# GATE_BOARD.net
KiCad netlist of a schematic drawn in Altium Designer
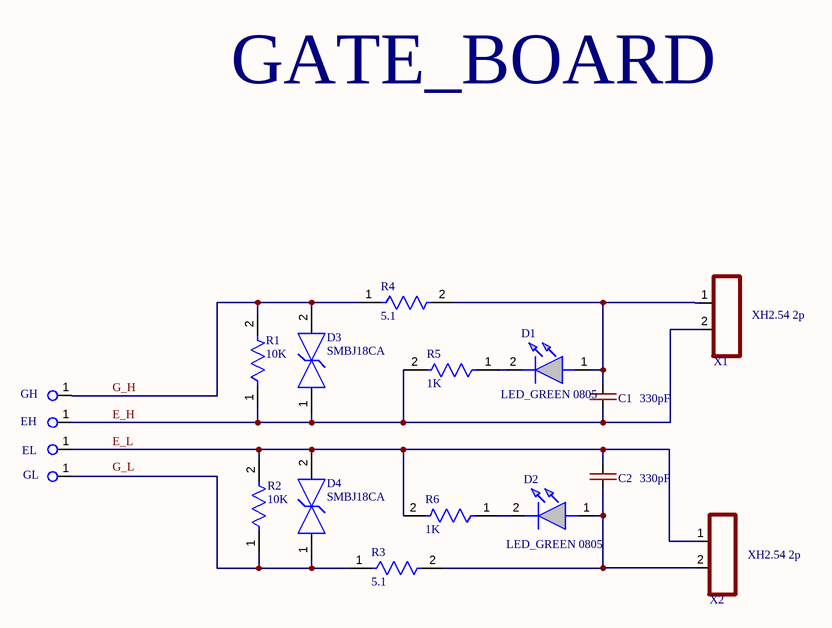
[diagram p0: GATE_BOARD.SchDoc]

(export (version "E")
  (design (tool "Eeschema 10.0.6"))
  (components
    (comp (ref "C1")
      (value "330pF")
      (footprint "CAP-0805")
      (libsource (lib "PASSIVE_COMPONENTS") (part "CAP-NON-POLAR"))
    )
    (comp (ref "C2")
      (value "330pF")
      (footprint "CAP-0805")
      (libsource (lib "PASSIVE_COMPONENTS") (part "CAP-NON-POLAR"))
    )
    (comp (ref "D1")
      (value "LED_GREEN 0805")
      (footprint "LED_GREEN")
      (fields
        (field (name "MANUFACTURER_PART_NUMBER") "151031YS06000")
        (field (name "MOUSER PART NUMBER") "710-151031YS06000")
      )
      (libsource (lib "Optic-LED") (part "LED"))
    )
    (comp (ref "D2")
      (value "LED_GREEN 0805")
      (footprint "LED_GREEN")
      (fields
        (field (name "MANUFACTURER_PART_NUMBER") "151031YS06000")
        (field (name "MOUSER PART NUMBER") "710-151031YS06000")
      )
      (libsource (lib "Optic-LED") (part "LED"))
    )
    (comp (ref "D3")
      (value "SMBJ18CA")
      (footprint "FP-SMBJ-MFG")
      (description "TVS DIODE 18V 29.2V DO214AA")
      (fields
        (field (name "MANUFACTURER") "Littelfuse Inc")
        (field (name "OCTOPART") "https://octopart.com/smbj18ca-littelfuse-350695")
      )
      (libsource (lib "Altium Content Vault") (part "876f4347bf90aa6f500f43e3cd03972"))
    )
    (comp (ref "D4")
      (value "SMBJ18CA")
      (footprint "FP-SMBJ-MFG")
      (description "TVS DIODE 18V 29.2V DO214AA")
      (fields
        (field (name "MANUFACTURER") "Littelfuse Inc")
        (field (name "OCTOPART") "https://octopart.com/smbj18ca-littelfuse-350695")
      )
      (libsource (lib "Altium Content Vault") (part "876f4347bf90aa6f500f43e3cd03972"))
    )
    (comp (ref "EH")
      (value "Test_Point_PCB")
      (footprint "Conn_Pad")
      (description "Test_Point")
      (libsource (lib "Connectors") (part "TP_PCB?"))
    )
    (comp (ref "EL")
      (value "Test_Point_PCB")
      (footprint "Conn_Pad")
      (description "Test_Point")
      (libsource (lib "Connectors") (part "TP_PCB?"))
    )
    (comp (ref "GL")
      (value "Test_Point_PCB")
      (footprint "Conn_Pad")
      (description "Test_Point")
      (libsource (lib "Connectors") (part "TP_PCB?"))
    )
    (comp (ref "R1")
      (value "10K")
      (footprint "RES-1206")
      (libsource (lib "PASSIVE_COMPONENTS") (part "RES-CONST"))
    )
    (comp (ref "R2")
      (value "10K")
      (footprint "RES-1206")
      (libsource (lib "PASSIVE_COMPONENTS") (part "RES-CONST"))
    )
    (comp (ref "R3")
      (value "5.1")
      (footprint "RES-2512")
      (libsource (lib "PASSIVE_COMPONENTS") (part "RES-CONST"))
    )
    (comp (ref "R4")
      (value "5.1")
      (footprint "RES-2512")
      (libsource (lib "PASSIVE_COMPONENTS") (part "RES-CONST"))
    )
    (comp (ref "R5")
      (value "1K")
      (footprint "RES-0805")
      (libsource (lib "PASSIVE_COMPONENTS") (part "RES-CONST"))
    )
    (comp (ref "R6")
      (value "1K")
      (footprint "RES-0805")
      (libsource (lib "PASSIVE_COMPONENTS") (part "RES-CONST"))
    )
    (comp (ref "TP4")
      (value "GH")
      (footprint "Conn_Pad")
      (description "Test_Point")
      (libsource (lib "Connectors") (part "TP_PCB?"))
    )
    (comp (ref "X1")
      (value "XH2.54 2p")
      (footprint "CONN-PLS-2-2.54mm")
      (libsource (lib "XH 2PIN") (part "CONN-2-PIN"))
    )
    (comp (ref "X2")
      (value "XH2.54 2p")
      (footprint "CONN-PLS-2-2.54mm")
      (libsource (lib "XH 2PIN") (part "CONN-2-PIN"))
    )
  )
  (nets
    (net (code "1") (name "/E_H") (class "Default")
      (node (ref "C1") (pin "1") (pinfunction "1_1") (pintype "passive"))
      (node (ref "D3") (pin "1") (pinfunction "1_1") (pintype "passive"))
      (node (ref "EH") (pin "1") (pinfunction "G9_1") (pintype "passive"))
      (node (ref "R1") (pin "1") (pinfunction "1_1") (pintype "passive"))
      (node (ref "R5") (pin "2") (pinfunction "2_2") (pintype "passive"))
      (node (ref "X1") (pin "2") (pinfunction "2_2") (pintype "passive"))
    )
    (net (code "2") (name "/E_L") (class "Default")
      (node (ref "C2") (pin "2") (pinfunction "2_2") (pintype "passive"))
      (node (ref "D4") (pin "2") (pinfunction "2_2") (pintype "passive"))
      (node (ref "EL") (pin "1") (pinfunction "G9_1") (pintype "passive"))
      (node (ref "R2") (pin "2") (pinfunction "2_2") (pintype "passive"))
      (node (ref "R6") (pin "2") (pinfunction "2_2") (pintype "passive"))
      (node (ref "X2") (pin "1") (pinfunction "1_1") (pintype "passive"))
    )
    (net (code "5") (name "/G_H") (class "Default")
      (node (ref "D3") (pin "2") (pinfunction "2_2") (pintype "passive"))
      (node (ref "R1") (pin "2") (pinfunction "2_2") (pintype "passive"))
      (node (ref "R4") (pin "1") (pinfunction "1_1") (pintype "passive"))
      (node (ref "TP4") (pin "1") (pinfunction "G9_1") (pintype "passive"))
    )
    (net (code "6") (name "Net-(D1-A)") (class "Default")
      (node (ref "C1") (pin "2") (pinfunction "2_2") (pintype "passive"))
      (node (ref "D1") (pin "1") (pinfunction "A_1") (pintype "passive"))
      (node (ref "R4") (pin "2") (pinfunction "2_2") (pintype "passive"))
      (node (ref "X1") (pin "1") (pinfunction "1_1") (pintype "passive"))
    )
    (net (code "7") (name "Net-(D1-K)") (class "Default")
      (node (ref "D1") (pin "2") (pinfunction "K_2") (pintype "passive"))
      (node (ref "R5") (pin "1") (pinfunction "1_1") (pintype "passive"))
    )
    (net (code "8") (name "Net-(D2-A)") (class "Default")
      (node (ref "C2") (pin "1") (pinfunction "1_1") (pintype "passive"))
      (node (ref "D2") (pin "1") (pinfunction "A_1") (pintype "passive"))
      (node (ref "R3") (pin "2") (pinfunction "2_2") (pintype "passive"))
      (node (ref "X2") (pin "2") (pinfunction "2_2") (pintype "passive"))
    )
    (net (code "9") (name "Net-(D2-K)") (class "Default")
      (node (ref "D2") (pin "2") (pinfunction "K_2") (pintype "passive"))
      (node (ref "R6") (pin "1") (pinfunction "1_1") (pintype "passive"))
    )
    (net (code "10") (name "Net-(GL-G9)") (class "Default")
      (node (ref "D4") (pin "1") (pinfunction "1_1") (pintype "passive"))
      (node (ref "GL") (pin "1") (pinfunction "G9_1") (pintype "passive"))
      (node (ref "R2") (pin "1") (pinfunction "1_1") (pintype "passive"))
      (node (ref "R3") (pin "1") (pinfunction "1_1") (pintype "passive"))
    )
  )
)
